# MPU-6050_SCHEMATIC.net
KiCad netlist of a schematic drawn in Altium Designer
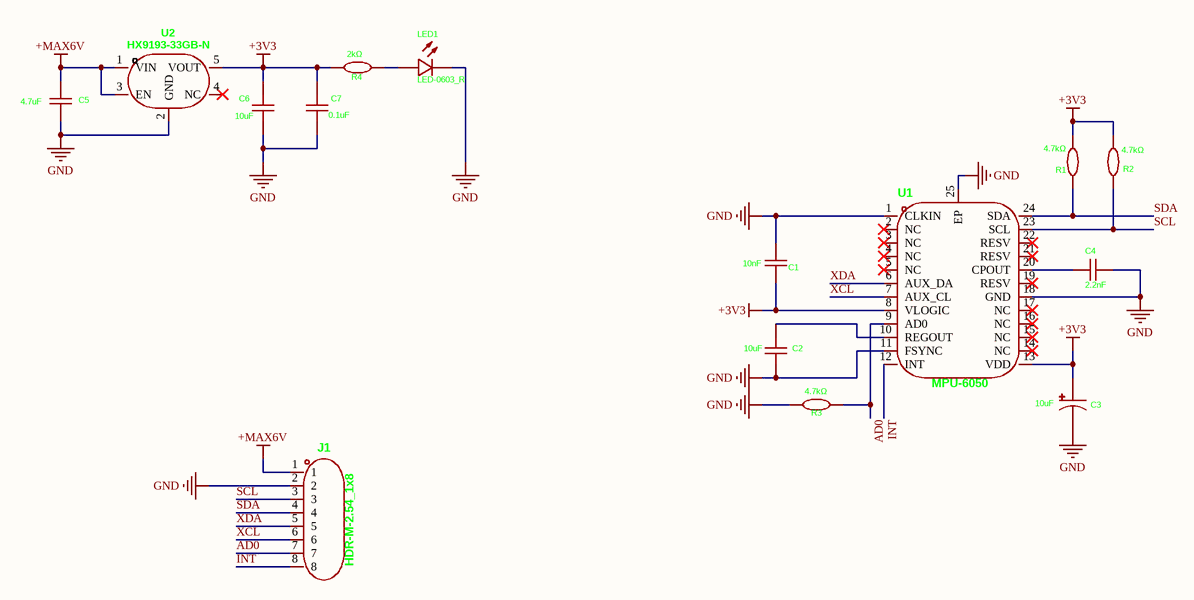
[diagram p0: MPU-6050_SCHEMATIC.SchDoc]

(export (version "E")
  (design (tool "Eeschema 10.0.6"))
  (components
    (comp (ref "C1")
      (value "10nF")
      (footprint "C0402-10N F")
      (description "50V 10nF X7R ±10% 0402 Multilayer Ceramic Capacitors MLCC - SMD/SMT ROHS")
      (fields
        (field (name "MANUFACTURER") "SAMSUNG(三星)")
        (field (name "MANUFACTURER PART") "CL05B103KB5NNNC")
      )
      (libsource (lib "Schlib1") (part "CL05B103KB5NNNC"))
    )
    (comp (ref "C2")
      (value "10uF")
      (footprint "C0402-10u F")
      (description "10V 10uF X5R ±20% 0402 Multilayer Ceramic Capacitors MLCC - SMD/SMT ROHS")
      (fields
        (field (name "MANUFACTURER") "SAMSUNG(三星)")
        (field (name "MANUFACTURER PART") "CL05A106MP5NUNC")
      )
      (libsource (lib "Schlib1") (part "CL05A106MP5NUNC_C315248"))
    )
    (comp (ref "C3")
      (value "10uF")
      (footprint "CAP-SMD_L3.2-W1.6-10u F")
      (description "10uF 16V 1Ω@100kHz ±10% CASE-A-3216-18(mm) Tantalum Capacitors ROHS")
      (fields
        (field (name "MANUFACTURER") "Kyocera AVX")
        (field (name "MANUFACTURER PART") "TPSA106K016R1000")
      )
      (libsource (lib "Schlib1") (part "TPSA106K016R1000_C282116"))
    )
    (comp (ref "C4")
      (value "2.2nF")
      (footprint "C0402-2.2n F")
      (description "50V 2.2nF X7R ±10% 0402 Multilayer Ceramic Capacitors MLCC - SMD/SMT ROHS")
      (fields
        (field (name "MANUFACTURER") "muRata(村田)")
        (field (name "MANUFACTURER PART") "GCM155R71H222KA37D")
      )
      (libsource (lib "Schlib1") (part "GCM155R71H222KA37D"))
    )
    (comp (ref "C5")
      (value "4.7uF")
      (footprint "C0402-4.7U F")
      (description "10V 4.7uF X5R ±20% 0402 Multilayer Ceramic Capacitors MLCC - SMD/SMT ROHS")
      (fields
        (field (name "MANUFACTURER") "SAMSUNG(三星)")
        (field (name "MANUFACTURER PART") "CL05A475MP5NRNC")
      )
      (libsource (lib "Schlib1") (part "CL05A475MP5NRNC"))
    )
    (comp (ref "C6")
      (value "10uF")
      (footprint "C0402-10u F")
      (description "10V 10uF X5R ±20% 0402 Multilayer Ceramic Capacitors MLCC - SMD/SMT ROHS")
      (fields
        (field (name "MANUFACTURER") "SAMSUNG(三星)")
        (field (name "MANUFACTURER PART") "CL05A106MP5NUNC")
      )
      (libsource (lib "Schlib1") (part "CL05A106MP5NUNC_C315248"))
    )
    (comp (ref "C7")
      (value "0.1uF")
      (footprint "C0402-0.1u f")
      (description "50V 100nF X7R ±10% 0402 Multilayer Ceramic Capacitors MLCC - SMD/SMT ROHS")
      (fields
        (field (name "MANUFACTURER") "muRata(村田)")
        (field (name "MANUFACTURER PART") "GRM155R71H104KE14D")
      )
      (libsource (lib "Schlib1") (part "GRM155R71H104KE14D"))
    )
    (comp (ref "J1")
      (value "HDR-M-2.54_1x8")
      (footprint "HDR-TH_8P-P2.54-V-M")
      (fields
        (field (name "MANUFACTURER") "Nextron(正凌)")
        (field (name "MANUFACTURER PART") "Z-211-0811-0021-001")
      )
      (libsource (lib "Schlib1") (part "Z-211-0811-0021-001"))
    )
    (comp (ref "LED1")
      (value "LED-0603_R")
      (footprint "LED0603-RD")
      (fields
        (field (name "MANUFACTURER") "EVERLIGHT(亿光)")
        (field (name "MANUFACTURER PART") "19-217/R6C-AL1M2VY/3T")
      )
      (libsource (lib "Schlib1") (part "19-217/R6C-AL1M2VY/3T"))
    )
    (comp (ref "R1")
      (value "4.7kΩ")
      (footprint "R0402-4.7K ohm")
      (description "62.5mW Thick Film Resistors 50V ±100ppm/℃ ±1% 4.7kΩ 0402 Chip Resistor - Surface Mount ROHS")
      (fields (field (name "MANUFACTURER") "YAGEO(国巨)") (field (name "MANUFACTURER PART") "RC0402FR-074K7L"))
      (libsource (lib "Schlib1") (part "RC0402FR-074K7L"))
    )
    (comp (ref "R2")
      (value "4.7kΩ")
      (footprint "R0402-4.7K ohm")
      (description "62.5mW Thick Film Resistors 50V ±100ppm/℃ ±1% 4.7kΩ 0402 Chip Resistor - Surface Mount ROHS")
      (fields (field (name "MANUFACTURER") "YAGEO(国巨)") (field (name "MANUFACTURER PART") "RC0402FR-074K7L"))
      (libsource (lib "Schlib1") (part "RC0402FR-074K7L"))
    )
    (comp (ref "R3")
      (value "4.7kΩ")
      (footprint "R0402-4.7K ohm")
      (description "62.5mW Thick Film Resistors 50V ±100ppm/℃ ±1% 4.7kΩ 0402 Chip Resistor - Surface Mount ROHS")
      (fields (field (name "MANUFACTURER") "YAGEO(国巨)") (field (name "MANUFACTURER PART") "RC0402FR-074K7L"))
      (libsource (lib "Schlib1") (part "RC0402FR-074K7L"))
    )
    (comp (ref "R4")
      (value "2kΩ")
      (footprint "R0402-2.2K OHM")
      (description "62.5mW Thick Film Resistors 50V ±100ppm/℃ ±1% 2kΩ 0402 Chip Resistor - Surface Mount ROHS")
      (fields (field (name "MANUFACTURER") "YAGEO(国巨)") (field (name "MANUFACTURER PART") "RC0402FR-072KL"))
      (libsource (lib "Schlib1") (part "RC0402FR-072KL"))
    )
    (comp (ref "U1")
      (value "MPU-6050")
      (footprint "QFN-24_L4.0-W4.0-P0.50-BL-EP2.7")
      (description "Accelerometer gyroscope QFN-24-EP(4x4) Accelerometers ROHS")
      (fields (field (name "MANUFACTURER") "TDK InvenSense(应美盛)"))
      (libsource (lib "Schlib1") (part "MPU-6050"))
    )
    (comp (ref "U2")
      (value "HX9193-33GB-N")
      (footprint "SOT-23-5_L2.9-W1.6-P0.95-LS2.8-BL")
      (description "300mA Fixed 3.3V 7V SOT-23-5 Voltage Regulators - Linear, Low Drop Out (LDO) Regulators ROHS")
      (fields (field (name "MANUFACTURER") "HX(恒佳兴)"))
      (libsource (lib "Schlib1") (part "HX9193-33GB-N"))
    )
  )
  (nets
    (net (code "1") (name "+3V3") (class "Default")
      (node (ref "C1") (pin "1") (pinfunction "1_1") (pintype "passive"))
      (node (ref "C3") (pin "1") (pinfunction "1_1") (pintype "passive"))
      (node (ref "C6") (pin "2") (pinfunction "2_2") (pintype "passive"))
      (node (ref "C7") (pin "2") (pinfunction "2_2") (pintype "passive"))
      (node (ref "R1") (pin "2") (pinfunction "2_2") (pintype "passive"))
      (node (ref "R2") (pin "2") (pinfunction "2_2") (pintype "passive"))
      (node (ref "R4") (pin "1") (pinfunction "1_1") (pintype "passive"))
      (node (ref "U1") (pin "13") (pinfunction "VDD_13") (pintype "passive"))
      (node (ref "U1") (pin "8") (pinfunction "VLOGIC_8") (pintype "passive"))
      (node (ref "U2") (pin "5") (pinfunction "VOUT_5") (pintype "passive"))
    )
    (net (code "2") (name "+MAX6V") (class "Default")
      (node (ref "C5") (pin "2") (pinfunction "2_2") (pintype "passive"))
      (node (ref "J1") (pin "1") (pinfunction "1_1") (pintype "passive"))
      (node (ref "U2") (pin "1") (pinfunction "VIN_1") (pintype "passive"))
      (node (ref "U2") (pin "3") (pinfunction "EN_3") (pintype "passive"))
    )
    (net (code "3") (name "/AD0") (class "Default")
      (node (ref "J1") (pin "7") (pinfunction "7_7") (pintype "passive"))
      (node (ref "R3") (pin "2") (pinfunction "2_2") (pintype "passive"))
      (node (ref "U1") (pin "9") (pinfunction "AD0_9") (pintype "passive"))
    )
    (net (code "4") (name "/INT") (class "Default")
      (node (ref "J1") (pin "8") (pinfunction "8_8") (pintype "passive"))
      (node (ref "U1") (pin "12") (pinfunction "INT_12") (pintype "passive"))
    )
    (net (code "5") (name "/SCL") (class "Default")
      (node (ref "J1") (pin "3") (pinfunction "3_3") (pintype "passive"))
      (node (ref "R2") (pin "1") (pinfunction "1_1") (pintype "passive"))
      (node (ref "U1") (pin "23") (pinfunction "SCL_23") (pintype "passive"))
    )
    (net (code "6") (name "/SDA") (class "Default")
      (node (ref "J1") (pin "4") (pinfunction "4_4") (pintype "passive"))
      (node (ref "R1") (pin "1") (pinfunction "1_1") (pintype "passive"))
      (node (ref "U1") (pin "24") (pinfunction "SDA_24") (pintype "passive"))
    )
    (net (code "7") (name "/XCL") (class "Default")
      (node (ref "J1") (pin "6") (pinfunction "6_6") (pintype "passive"))
      (node (ref "U1") (pin "7") (pinfunction "AUX_CL_7") (pintype "passive"))
    )
    (net (code "8") (name "/XDA") (class "Default")
      (node (ref "J1") (pin "5") (pinfunction "5_5") (pintype "passive"))
      (node (ref "U1") (pin "6") (pinfunction "AUX_DA_6") (pintype "passive"))
    )
    (net (code "9") (name "GND") (class "Default")
      (node (ref "C1") (pin "2") (pinfunction "2_2") (pintype "passive"))
      (node (ref "C2") (pin "1") (pinfunction "1_1") (pintype "passive"))
      (node (ref "C3") (pin "2") (pinfunction "2_2") (pintype "passive"))
      (node (ref "C4") (pin "1") (pinfunction "1_1") (pintype "passive"))
      (node (ref "C5") (pin "1") (pinfunction "1_1") (pintype "passive"))
      (node (ref "C6") (pin "1") (pinfunction "1_1") (pintype "passive"))
      (node (ref "C7") (pin "1") (pinfunction "1_1") (pintype "passive"))
      (node (ref "J1") (pin "2") (pinfunction "2_2") (pintype "passive"))
      (node (ref "LED1") (pin "1") (pinfunction "C_1") (pintype "passive"))
      (node (ref "R3") (pin "1") (pinfunction "1_1") (pintype "passive"))
      (node (ref "U1") (pin "1") (pinfunction "CLKIN_1") (pintype "passive"))
      (node (ref "U1") (pin "11") (pinfunction "FSYNC_11") (pintype "passive"))
      (node (ref "U1") (pin "18") (pinfunction "GND_18") (pintype "passive"))
      (node (ref "U1") (pin "25") (pinfunction "EP_25") (pintype "passive"))
      (node (ref "U2") (pin "2") (pinfunction "GND_2") (pintype "passive"))
    )
    (net (code "10") (name "Net-(LED1-A)") (class "Default")
      (node (ref "LED1") (pin "2") (pinfunction "A_2") (pintype "passive"))
      (node (ref "R4") (pin "2") (pinfunction "2_2") (pintype "passive"))
    )
    (net (code "11") (name "Net-(U1-CPOUT)") (class "Default")
      (node (ref "C4") (pin "2") (pinfunction "2_2") (pintype "passive"))
      (node (ref "U1") (pin "20") (pinfunction "CPOUT_20") (pintype "passive"))
    )
    (net (code "12") (name "Net-(U1-REGOUT)") (class "Default")
      (node (ref "C2") (pin "2") (pinfunction "2_2") (pintype "passive"))
      (node (ref "U1") (pin "10") (pinfunction "REGOUT_10") (pintype "passive"))
    )
    (net (code "13") (name "unconnected-(U1-NC-Pad2)") (class "Default")
      (node (ref "U1") (pin "2") (pinfunction "NC_2") (pintype "passive+no_connect"))
    )
    (net (code "14") (name "unconnected-(U1-NC-Pad3)") (class "Default")
      (node (ref "U1") (pin "3") (pinfunction "NC_3") (pintype "passive+no_connect"))
    )
    (net (code "15") (name "unconnected-(U1-NC-Pad4)") (class "Default")
      (node (ref "U1") (pin "4") (pinfunction "NC_4") (pintype "passive+no_connect"))
    )
    (net (code "16") (name "unconnected-(U1-NC-Pad5)") (class "Default")
      (node (ref "U1") (pin "5") (pinfunction "NC_5") (pintype "passive+no_connect"))
    )
    (net (code "17") (name "unconnected-(U1-NC-Pad14)") (class "Default")
      (node (ref "U1") (pin "14") (pinfunction "NC_14") (pintype "passive+no_connect"))
    )
    (net (code "18") (name "unconnected-(U1-NC-Pad15)") (class "Default")
      (node (ref "U1") (pin "15") (pinfunction "NC_15") (pintype "passive+no_connect"))
    )
    (net (code "19") (name "unconnected-(U1-NC-Pad16)") (class "Default")
      (node (ref "U1") (pin "16") (pinfunction "NC_16") (pintype "passive+no_connect"))
    )
    (net (code "20") (name "unconnected-(U1-NC-Pad17)") (class "Default")
      (node (ref "U1") (pin "17") (pinfunction "NC_17") (pintype "passive+no_connect"))
    )
    (net (code "21") (name "unconnected-(U1-RESV-Pad19)") (class "Default")
      (node (ref "U1") (pin "19") (pinfunction "RESV_19") (pintype "passive+no_connect"))
    )
    (net (code "22") (name "unconnected-(U1-RESV-Pad21)") (class "Default")
      (node (ref "U1") (pin "21") (pinfunction "RESV_21") (pintype "passive+no_connect"))
    )
    (net (code "23") (name "unconnected-(U1-RESV-Pad22)") (class "Default")
      (node (ref "U1") (pin "22") (pinfunction "RESV_22") (pintype "passive+no_connect"))
    )
    (net (code "24") (name "unconnected-(U2-NC-Pad4)") (class "Default")
      (node (ref "U2") (pin "4") (pinfunction "NC_4") (pintype "passive+no_connect"))
    )
  )
)
